# BlueLed.net
KiCad netlist of a schematic drawn in Altium Designer
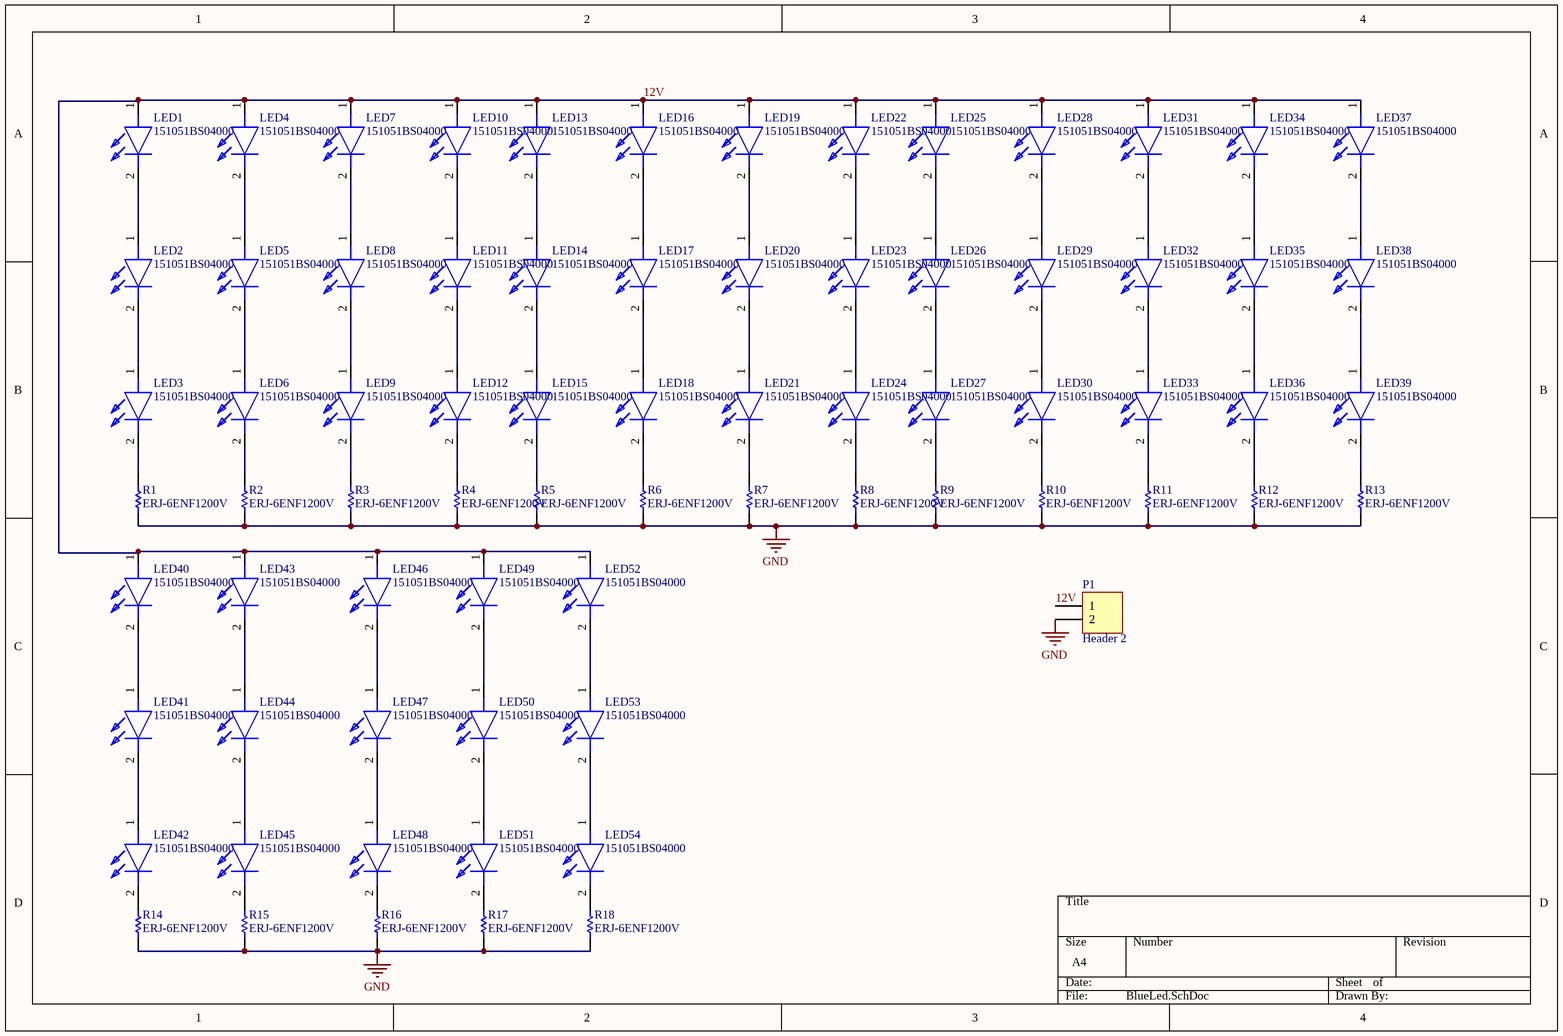
[diagram p0: BlueLed.SchDoc]

(export (version "E")
  (design (tool "Eeschema 10.0.6"))
  (components
    (comp (ref "LED1")
      (value "151051BS04000")
      (footprint "SamacSys:151051BS04000")
      (description "LED")
      (fields (field (name "MOUSER PART NUMBER") "710-151051BS04000"))
      (libsource (lib "*") (part "151051BS04000"))
    )
    (comp (ref "LED2")
      (value "151051BS04000")
      (footprint "SamacSys:151051BS04000")
      (description "LED")
      (fields (field (name "MOUSER PART NUMBER") "710-151051BS04000"))
      (libsource (lib "*") (part "151051BS04000"))
    )
    (comp (ref "LED3")
      (value "151051BS04000")
      (footprint "SamacSys:151051BS04000")
      (description "LED")
      (fields (field (name "MOUSER PART NUMBER") "710-151051BS04000"))
      (libsource (lib "*") (part "151051BS04000"))
    )
    (comp (ref "LED4")
      (value "151051BS04000")
      (footprint "SamacSys:151051BS04000")
      (description "LED")
      (fields (field (name "MOUSER PART NUMBER") "710-151051BS04000"))
      (libsource (lib "*") (part "151051BS04000"))
    )
    (comp (ref "LED5")
      (value "151051BS04000")
      (footprint "SamacSys:151051BS04000")
      (description "LED")
      (fields (field (name "MOUSER PART NUMBER") "710-151051BS04000"))
      (libsource (lib "*") (part "151051BS04000"))
    )
    (comp (ref "LED6")
      (value "151051BS04000")
      (footprint "SamacSys:151051BS04000")
      (description "LED")
      (fields (field (name "MOUSER PART NUMBER") "710-151051BS04000"))
      (libsource (lib "*") (part "151051BS04000"))
    )
    (comp (ref "LED7")
      (value "151051BS04000")
      (footprint "SamacSys:151051BS04000")
      (description "LED")
      (fields (field (name "MOUSER PART NUMBER") "710-151051BS04000"))
      (libsource (lib "*") (part "151051BS04000"))
    )
    (comp (ref "LED8")
      (value "151051BS04000")
      (footprint "SamacSys:151051BS04000")
      (description "LED")
      (fields (field (name "MOUSER PART NUMBER") "710-151051BS04000"))
      (libsource (lib "*") (part "151051BS04000"))
    )
    (comp (ref "LED9")
      (value "151051BS04000")
      (footprint "SamacSys:151051BS04000")
      (description "LED")
      (fields (field (name "MOUSER PART NUMBER") "710-151051BS04000"))
      (libsource (lib "*") (part "151051BS04000"))
    )
    (comp (ref "LED10")
      (value "151051BS04000")
      (footprint "SamacSys:151051BS04000")
      (description "LED")
      (fields (field (name "MOUSER PART NUMBER") "710-151051BS04000"))
      (libsource (lib "*") (part "151051BS04000"))
    )
    (comp (ref "LED11")
      (value "151051BS04000")
      (footprint "SamacSys:151051BS04000")
      (description "LED")
      (fields (field (name "MOUSER PART NUMBER") "710-151051BS04000"))
      (libsource (lib "*") (part "151051BS04000"))
    )
    (comp (ref "LED12")
      (value "151051BS04000")
      (footprint "SamacSys:151051BS04000")
      (description "LED")
      (fields (field (name "MOUSER PART NUMBER") "710-151051BS04000"))
      (libsource (lib "*") (part "151051BS04000"))
    )
    (comp (ref "LED13")
      (value "151051BS04000")
      (footprint "SamacSys:151051BS04000")
      (description "LED")
      (fields (field (name "MOUSER PART NUMBER") "710-151051BS04000"))
      (libsource (lib "*") (part "151051BS04000"))
    )
    (comp (ref "LED14")
      (value "151051BS04000")
      (footprint "SamacSys:151051BS04000")
      (description "LED")
      (fields (field (name "MOUSER PART NUMBER") "710-151051BS04000"))
      (libsource (lib "*") (part "151051BS04000"))
    )
    (comp (ref "LED15")
      (value "151051BS04000")
      (footprint "SamacSys:151051BS04000")
      (description "LED")
      (fields (field (name "MOUSER PART NUMBER") "710-151051BS04000"))
      (libsource (lib "*") (part "151051BS04000"))
    )
    (comp (ref "LED16")
      (value "151051BS04000")
      (footprint "SamacSys:151051BS04000")
      (description "LED")
      (fields (field (name "MOUSER PART NUMBER") "710-151051BS04000"))
      (libsource (lib "*") (part "151051BS04000"))
    )
    (comp (ref "LED17")
      (value "151051BS04000")
      (footprint "SamacSys:151051BS04000")
      (description "LED")
      (fields (field (name "MOUSER PART NUMBER") "710-151051BS04000"))
      (libsource (lib "*") (part "151051BS04000"))
    )
    (comp (ref "LED18")
      (value "151051BS04000")
      (footprint "SamacSys:151051BS04000")
      (description "LED")
      (fields (field (name "MOUSER PART NUMBER") "710-151051BS04000"))
      (libsource (lib "*") (part "151051BS04000"))
    )
    (comp (ref "LED19")
      (value "151051BS04000")
      (footprint "SamacSys:151051BS04000")
      (description "LED")
      (fields (field (name "MOUSER PART NUMBER") "710-151051BS04000"))
      (libsource (lib "*") (part "151051BS04000"))
    )
    (comp (ref "LED20")
      (value "151051BS04000")
      (footprint "SamacSys:151051BS04000")
      (description "LED")
      (fields (field (name "MOUSER PART NUMBER") "710-151051BS04000"))
      (libsource (lib "*") (part "151051BS04000"))
    )
    (comp (ref "LED21")
      (value "151051BS04000")
      (footprint "SamacSys:151051BS04000")
      (description "LED")
      (fields (field (name "MOUSER PART NUMBER") "710-151051BS04000"))
      (libsource (lib "*") (part "151051BS04000"))
    )
    (comp (ref "LED22")
      (value "151051BS04000")
      (footprint "SamacSys:151051BS04000")
      (description "LED")
      (fields (field (name "MOUSER PART NUMBER") "710-151051BS04000"))
      (libsource (lib "*") (part "151051BS04000"))
    )
    (comp (ref "LED23")
      (value "151051BS04000")
      (footprint "SamacSys:151051BS04000")
      (description "LED")
      (fields (field (name "MOUSER PART NUMBER") "710-151051BS04000"))
      (libsource (lib "*") (part "151051BS04000"))
    )
    (comp (ref "LED24")
      (value "151051BS04000")
      (footprint "SamacSys:151051BS04000")
      (description "LED")
      (fields (field (name "MOUSER PART NUMBER") "710-151051BS04000"))
      (libsource (lib "*") (part "151051BS04000"))
    )
    (comp (ref "LED25")
      (value "151051BS04000")
      (footprint "SamacSys:151051BS04000")
      (description "LED")
      (fields (field (name "MOUSER PART NUMBER") "710-151051BS04000"))
      (libsource (lib "*") (part "151051BS04000"))
    )
    (comp (ref "LED26")
      (value "151051BS04000")
      (footprint "SamacSys:151051BS04000")
      (description "LED")
      (fields (field (name "MOUSER PART NUMBER") "710-151051BS04000"))
      (libsource (lib "*") (part "151051BS04000"))
    )
    (comp (ref "LED27")
      (value "151051BS04000")
      (footprint "SamacSys:151051BS04000")
      (description "LED")
      (fields (field (name "MOUSER PART NUMBER") "710-151051BS04000"))
      (libsource (lib "*") (part "151051BS04000"))
    )
    (comp (ref "LED28")
      (value "151051BS04000")
      (footprint "SamacSys:151051BS04000")
      (description "LED")
      (fields (field (name "MOUSER PART NUMBER") "710-151051BS04000"))
      (libsource (lib "*") (part "151051BS04000"))
    )
    (comp (ref "LED29")
      (value "151051BS04000")
      (footprint "SamacSys:151051BS04000")
      (description "LED")
      (fields (field (name "MOUSER PART NUMBER") "710-151051BS04000"))
      (libsource (lib "*") (part "151051BS04000"))
    )
    (comp (ref "LED30")
      (value "151051BS04000")
      (footprint "SamacSys:151051BS04000")
      (description "LED")
      (fields (field (name "MOUSER PART NUMBER") "710-151051BS04000"))
      (libsource (lib "*") (part "151051BS04000"))
    )
    (comp (ref "LED31")
      (value "151051BS04000")
      (footprint "SamacSys:151051BS04000")
      (description "LED")
      (fields (field (name "MOUSER PART NUMBER") "710-151051BS04000"))
      (libsource (lib "*") (part "151051BS04000"))
    )
    (comp (ref "LED32")
      (value "151051BS04000")
      (footprint "SamacSys:151051BS04000")
      (description "LED")
      (fields (field (name "MOUSER PART NUMBER") "710-151051BS04000"))
      (libsource (lib "*") (part "151051BS04000"))
    )
    (comp (ref "LED33")
      (value "151051BS04000")
      (footprint "SamacSys:151051BS04000")
      (description "LED")
      (fields (field (name "MOUSER PART NUMBER") "710-151051BS04000"))
      (libsource (lib "*") (part "151051BS04000"))
    )
    (comp (ref "LED34")
      (value "151051BS04000")
      (footprint "SamacSys:151051BS04000")
      (description "LED")
      (fields (field (name "MOUSER PART NUMBER") "710-151051BS04000"))
      (libsource (lib "*") (part "151051BS04000"))
    )
    (comp (ref "LED35")
      (value "151051BS04000")
      (footprint "SamacSys:151051BS04000")
      (description "LED")
      (fields (field (name "MOUSER PART NUMBER") "710-151051BS04000"))
      (libsource (lib "*") (part "151051BS04000"))
    )
    (comp (ref "LED36")
      (value "151051BS04000")
      (footprint "SamacSys:151051BS04000")
      (description "LED")
      (fields (field (name "MOUSER PART NUMBER") "710-151051BS04000"))
      (libsource (lib "*") (part "151051BS04000"))
    )
    (comp (ref "LED37")
      (value "151051BS04000")
      (footprint "SamacSys:151051BS04000")
      (description "LED")
      (fields (field (name "MOUSER PART NUMBER") "710-151051BS04000"))
      (libsource (lib "*") (part "151051BS04000"))
    )
    (comp (ref "LED38")
      (value "151051BS04000")
      (footprint "SamacSys:151051BS04000")
      (description "LED")
      (fields (field (name "MOUSER PART NUMBER") "710-151051BS04000"))
      (libsource (lib "*") (part "151051BS04000"))
    )
    (comp (ref "LED39")
      (value "151051BS04000")
      (footprint "SamacSys:151051BS04000")
      (description "LED")
      (fields (field (name "MOUSER PART NUMBER") "710-151051BS04000"))
      (libsource (lib "*") (part "151051BS04000"))
    )
    (comp (ref "LED40")
      (value "151051BS04000")
      (footprint "SamacSys:151051BS04000")
      (description "LED")
      (fields (field (name "MOUSER PART NUMBER") "710-151051BS04000"))
      (libsource (lib "*") (part "151051BS04000"))
    )
    (comp (ref "LED41")
      (value "151051BS04000")
      (footprint "SamacSys:151051BS04000")
      (description "LED")
      (fields (field (name "MOUSER PART NUMBER") "710-151051BS04000"))
      (libsource (lib "*") (part "151051BS04000"))
    )
    (comp (ref "LED42")
      (value "151051BS04000")
      (footprint "SamacSys:151051BS04000")
      (description "LED")
      (fields (field (name "MOUSER PART NUMBER") "710-151051BS04000"))
      (libsource (lib "*") (part "151051BS04000"))
    )
    (comp (ref "LED43")
      (value "151051BS04000")
      (footprint "SamacSys:151051BS04000")
      (description "LED")
      (fields (field (name "MOUSER PART NUMBER") "710-151051BS04000"))
      (libsource (lib "*") (part "151051BS04000"))
    )
    (comp (ref "LED44")
      (value "151051BS04000")
      (footprint "SamacSys:151051BS04000")
      (description "LED")
      (fields (field (name "MOUSER PART NUMBER") "710-151051BS04000"))
      (libsource (lib "*") (part "151051BS04000"))
    )
    (comp (ref "LED45")
      (value "151051BS04000")
      (footprint "SamacSys:151051BS04000")
      (description "LED")
      (fields (field (name "MOUSER PART NUMBER") "710-151051BS04000"))
      (libsource (lib "*") (part "151051BS04000"))
    )
    (comp (ref "LED46")
      (value "151051BS04000")
      (footprint "SamacSys:151051BS04000")
      (description "LED")
      (fields (field (name "MOUSER PART NUMBER") "710-151051BS04000"))
      (libsource (lib "*") (part "151051BS04000"))
    )
    (comp (ref "LED47")
      (value "151051BS04000")
      (footprint "SamacSys:151051BS04000")
      (description "LED")
      (fields (field (name "MOUSER PART NUMBER") "710-151051BS04000"))
      (libsource (lib "*") (part "151051BS04000"))
    )
    (comp (ref "LED48")
      (value "151051BS04000")
      (footprint "SamacSys:151051BS04000")
      (description "LED")
      (fields (field (name "MOUSER PART NUMBER") "710-151051BS04000"))
      (libsource (lib "*") (part "151051BS04000"))
    )
    (comp (ref "LED49")
      (value "151051BS04000")
      (footprint "SamacSys:151051BS04000")
      (description "LED")
      (fields (field (name "MOUSER PART NUMBER") "710-151051BS04000"))
      (libsource (lib "*") (part "151051BS04000"))
    )
    (comp (ref "LED50")
      (value "151051BS04000")
      (footprint "SamacSys:151051BS04000")
      (description "LED")
      (fields (field (name "MOUSER PART NUMBER") "710-151051BS04000"))
      (libsource (lib "*") (part "151051BS04000"))
    )
    (comp (ref "LED51")
      (value "151051BS04000")
      (footprint "SamacSys:151051BS04000")
      (description "LED")
      (fields (field (name "MOUSER PART NUMBER") "710-151051BS04000"))
      (libsource (lib "*") (part "151051BS04000"))
    )
    (comp (ref "LED52")
      (value "151051BS04000")
      (footprint "SamacSys:151051BS04000")
      (description "LED")
      (fields (field (name "MOUSER PART NUMBER") "710-151051BS04000"))
      (libsource (lib "*") (part "151051BS04000"))
    )
    (comp (ref "LED53")
      (value "151051BS04000")
      (footprint "SamacSys:151051BS04000")
      (description "LED")
      (fields (field (name "MOUSER PART NUMBER") "710-151051BS04000"))
      (libsource (lib "*") (part "151051BS04000"))
    )
    (comp (ref "LED54")
      (value "151051BS04000")
      (footprint "SamacSys:151051BS04000")
      (description "LED")
      (fields (field (name "MOUSER PART NUMBER") "710-151051BS04000"))
      (libsource (lib "*") (part "151051BS04000"))
    )
    (comp (ref "P1")
      (value "Header 2")
      (footprint "HDR1X2")
      (description "Header, 2-Pin")
      (fields (field (name "PUBLISHER") "Altium Limited"))
      (libsource (lib "Miscellaneous Connectors") (part "Header 2"))
    )
    (comp (ref "R1")
      (value "ERJ-6ENF1200V")
      (footprint "RESC2013X70X40NL20T20")
      (description "Chip Resistor, 120 Ohm, +/- 1%, 0.125 W, -55 to 155 degC, 0805 (2012 Metric), RoHS, Tape and Reel")
      (fields (field (name "MANUFACTURER") "Panasonic"))
      (libsource (lib "Altium Content Vault") (part "RES-2"))
    )
    (comp (ref "R2")
      (value "ERJ-6ENF1200V")
      (footprint "RESC2013X70X40NL20T20")
      (description "Chip Resistor, 120 Ohm, +/- 1%, 0.125 W, -55 to 155 degC, 0805 (2012 Metric), RoHS, Tape and Reel")
      (fields (field (name "MANUFACTURER") "Panasonic"))
      (libsource (lib "Altium Content Vault") (part "RES-2"))
    )
    (comp (ref "R3")
      (value "ERJ-6ENF1200V")
      (footprint "RESC2013X70X40NL20T20")
      (description "Chip Resistor, 120 Ohm, +/- 1%, 0.125 W, -55 to 155 degC, 0805 (2012 Metric), RoHS, Tape and Reel")
      (fields (field (name "MANUFACTURER") "Panasonic"))
      (libsource (lib "Altium Content Vault") (part "RES-2"))
    )
    (comp (ref "R4")
      (value "ERJ-6ENF1200V")
      (footprint "RESC2013X70X40NL20T20")
      (description "Chip Resistor, 120 Ohm, +/- 1%, 0.125 W, -55 to 155 degC, 0805 (2012 Metric), RoHS, Tape and Reel")
      (fields (field (name "MANUFACTURER") "Panasonic"))
      (libsource (lib "Altium Content Vault") (part "RES-2"))
    )
    (comp (ref "R5")
      (value "ERJ-6ENF1200V")
      (footprint "RESC2013X70X40NL20T20")
      (description "Chip Resistor, 120 Ohm, +/- 1%, 0.125 W, -55 to 155 degC, 0805 (2012 Metric), RoHS, Tape and Reel")
      (fields (field (name "MANUFACTURER") "Panasonic"))
      (libsource (lib "Altium Content Vault") (part "RES-2"))
    )
    (comp (ref "R6")
      (value "ERJ-6ENF1200V")
      (footprint "RESC2013X70X40NL20T20")
      (description "Chip Resistor, 120 Ohm, +/- 1%, 0.125 W, -55 to 155 degC, 0805 (2012 Metric), RoHS, Tape and Reel")
      (fields (field (name "MANUFACTURER") "Panasonic"))
      (libsource (lib "Altium Content Vault") (part "RES-2"))
    )
    (comp (ref "R7")
      (value "ERJ-6ENF1200V")
      (footprint "RESC2013X70X40NL20T20")
      (description "Chip Resistor, 120 Ohm, +/- 1%, 0.125 W, -55 to 155 degC, 0805 (2012 Metric), RoHS, Tape and Reel")
      (fields (field (name "MANUFACTURER") "Panasonic"))
      (libsource (lib "Altium Content Vault") (part "RES-2"))
    )
    (comp (ref "R8")
      (value "ERJ-6ENF1200V")
      (footprint "RESC2013X70X40NL20T20")
      (description "Chip Resistor, 120 Ohm, +/- 1%, 0.125 W, -55 to 155 degC, 0805 (2012 Metric), RoHS, Tape and Reel")
      (fields (field (name "MANUFACTURER") "Panasonic"))
      (libsource (lib "Altium Content Vault") (part "RES-2"))
    )
    (comp (ref "R9")
      (value "ERJ-6ENF1200V")
      (footprint "RESC2013X70X40NL20T20")
      (description "Chip Resistor, 120 Ohm, +/- 1%, 0.125 W, -55 to 155 degC, 0805 (2012 Metric), RoHS, Tape and Reel")
      (fields (field (name "MANUFACTURER") "Panasonic"))
      (libsource (lib "Altium Content Vault") (part "RES-2"))
    )
    (comp (ref "R10")
      (value "ERJ-6ENF1200V")
      (footprint "RESC2013X70X40NL20T20")
      (description "Chip Resistor, 120 Ohm, +/- 1%, 0.125 W, -55 to 155 degC, 0805 (2012 Metric), RoHS, Tape and Reel")
      (fields (field (name "MANUFACTURER") "Panasonic"))
      (libsource (lib "Altium Content Vault") (part "RES-2"))
    )
    (comp (ref "R11")
      (value "ERJ-6ENF1200V")
      (footprint "RESC2013X70X40NL20T20")
      (description "Chip Resistor, 120 Ohm, +/- 1%, 0.125 W, -55 to 155 degC, 0805 (2012 Metric), RoHS, Tape and Reel")
      (fields (field (name "MANUFACTURER") "Panasonic"))
      (libsource (lib "Altium Content Vault") (part "RES-2"))
    )
    (comp (ref "R12")
      (value "ERJ-6ENF1200V")
      (footprint "RESC2013X70X40NL20T20")
      (description "Chip Resistor, 120 Ohm, +/- 1%, 0.125 W, -55 to 155 degC, 0805 (2012 Metric), RoHS, Tape and Reel")
      (fields (field (name "MANUFACTURER") "Panasonic"))
      (libsource (lib "Altium Content Vault") (part "RES-2"))
    )
    (comp (ref "R13")
      (value "ERJ-6ENF1200V")
      (footprint "RESC2013X70X40NL20T20")
      (description "Chip Resistor, 120 Ohm, +/- 1%, 0.125 W, -55 to 155 degC, 0805 (2012 Metric), RoHS, Tape and Reel")
      (fields (field (name "MANUFACTURER") "Panasonic"))
      (libsource (lib "Altium Content Vault") (part "RES-2"))
    )
    (comp (ref "R14")
      (value "ERJ-6ENF1200V")
      (footprint "RESC2013X70X40NL20T20")
      (description "Chip Resistor, 120 Ohm, +/- 1%, 0.125 W, -55 to 155 degC, 0805 (2012 Metric), RoHS, Tape and Reel")
      (fields (field (name "MANUFACTURER") "Panasonic"))
      (libsource (lib "Altium Content Vault") (part "RES-2"))
    )
    (comp (ref "R15")
      (value "ERJ-6ENF1200V")
      (footprint "RESC2013X70X40NL20T20")
      (description "Chip Resistor, 120 Ohm, +/- 1%, 0.125 W, -55 to 155 degC, 0805 (2012 Metric), RoHS, Tape and Reel")
      (fields (field (name "MANUFACTURER") "Panasonic"))
      (libsource (lib "Altium Content Vault") (part "RES-2"))
    )
    (comp (ref "R16")
      (value "ERJ-6ENF1200V")
      (footprint "RESC2013X70X40NL20T20")
      (description "Chip Resistor, 120 Ohm, +/- 1%, 0.125 W, -55 to 155 degC, 0805 (2012 Metric), RoHS, Tape and Reel")
      (fields (field (name "MANUFACTURER") "Panasonic"))
      (libsource (lib "Altium Content Vault") (part "RES-2"))
    )
    (comp (ref "R17")
      (value "ERJ-6ENF1200V")
      (footprint "RESC2013X70X40NL20T20")
      (description "Chip Resistor, 120 Ohm, +/- 1%, 0.125 W, -55 to 155 degC, 0805 (2012 Metric), RoHS, Tape and Reel")
      (fields (field (name "MANUFACTURER") "Panasonic"))
      (libsource (lib "Altium Content Vault") (part "RES-2"))
    )
    (comp (ref "R18")
      (value "ERJ-6ENF1200V")
      (footprint "RESC2013X70X40NL20T20")
      (description "Chip Resistor, 120 Ohm, +/- 1%, 0.125 W, -55 to 155 degC, 0805 (2012 Metric), RoHS, Tape and Reel")
      (fields (field (name "MANUFACTURER") "Panasonic"))
      (libsource (lib "Altium Content Vault") (part "RES-2"))
    )
  )
  (nets
    (net (code "1") (name "/12V") (class "Default")
      (node (ref "LED1") (pin "1") (pinfunction "A_1") (pintype "passive"))
      (node (ref "LED10") (pin "1") (pinfunction "A_1") (pintype "passive"))
      (node (ref "LED13") (pin "1") (pinfunction "A_1") (pintype "passive"))
      (node (ref "LED16") (pin "1") (pinfunction "A_1") (pintype "passive"))
      (node (ref "LED19") (pin "1") (pinfunction "A_1") (pintype "passive"))
      (node (ref "LED22") (pin "1") (pinfunction "A_1") (pintype "passive"))
      (node (ref "LED25") (pin "1") (pinfunction "A_1") (pintype "passive"))
      (node (ref "LED28") (pin "1") (pinfunction "A_1") (pintype "passive"))
      (node (ref "LED31") (pin "1") (pinfunction "A_1") (pintype "passive"))
      (node (ref "LED34") (pin "1") (pinfunction "A_1") (pintype "passive"))
      (node (ref "LED37") (pin "1") (pinfunction "A_1") (pintype "passive"))
      (node (ref "LED4") (pin "1") (pinfunction "A_1") (pintype "passive"))
      (node (ref "LED40") (pin "1") (pinfunction "A_1") (pintype "passive"))
      (node (ref "LED43") (pin "1") (pinfunction "A_1") (pintype "passive"))
      (node (ref "LED46") (pin "1") (pinfunction "A_1") (pintype "passive"))
      (node (ref "LED49") (pin "1") (pinfunction "A_1") (pintype "passive"))
      (node (ref "LED52") (pin "1") (pinfunction "A_1") (pintype "passive"))
      (node (ref "LED7") (pin "1") (pinfunction "A_1") (pintype "passive"))
      (node (ref "P1") (pin "1") (pinfunction "1_1") (pintype "passive"))
    )
    (net (code "2") (name "GND") (class "Default")
      (node (ref "P1") (pin "2") (pinfunction "2_2") (pintype "passive"))
      (node (ref "R1") (pin "1") (pinfunction "1_1") (pintype "passive"))
      (node (ref "R10") (pin "1") (pinfunction "1_1") (pintype "passive"))
      (node (ref "R11") (pin "1") (pinfunction "1_1") (pintype "passive"))
      (node (ref "R12") (pin "1") (pinfunction "1_1") (pintype "passive"))
      (node (ref "R13") (pin "1") (pinfunction "1_1") (pintype "passive"))
      (node (ref "R14") (pin "1") (pinfunction "1_1") (pintype "passive"))
      (node (ref "R15") (pin "1") (pinfunction "1_1") (pintype "passive"))
      (node (ref "R16") (pin "1") (pinfunction "1_1") (pintype "passive"))
      (node (ref "R17") (pin "1") (pinfunction "1_1") (pintype "passive"))
      (node (ref "R18") (pin "1") (pinfunction "1_1") (pintype "passive"))
      (node (ref "R2") (pin "1") (pinfunction "1_1") (pintype "passive"))
      (node (ref "R3") (pin "1") (pinfunction "1_1") (pintype "passive"))
      (node (ref "R4") (pin "1") (pinfunction "1_1") (pintype "passive"))
      (node (ref "R5") (pin "1") (pinfunction "1_1") (pintype "passive"))
      (node (ref "R6") (pin "1") (pinfunction "1_1") (pintype "passive"))
      (node (ref "R7") (pin "1") (pinfunction "1_1") (pintype "passive"))
      (node (ref "R8") (pin "1") (pinfunction "1_1") (pintype "passive"))
      (node (ref "R9") (pin "1") (pinfunction "1_1") (pintype "passive"))
    )
    (net (code "3") (name "Net-(LED1-K)") (class "Default")
      (node (ref "LED1") (pin "2") (pinfunction "K_2") (pintype "passive"))
      (node (ref "LED2") (pin "1") (pinfunction "A_1") (pintype "passive"))
    )
    (net (code "4") (name "Net-(LED2-K)") (class "Default")
      (node (ref "LED2") (pin "2") (pinfunction "K_2") (pintype "passive"))
      (node (ref "LED3") (pin "1") (pinfunction "A_1") (pintype "passive"))
    )
    (net (code "5") (name "Net-(LED3-K)") (class "Default")
      (node (ref "LED3") (pin "2") (pinfunction "K_2") (pintype "passive"))
      (node (ref "R1") (pin "2") (pinfunction "2_2") (pintype "passive"))
    )
    (net (code "6") (name "Net-(LED4-K)") (class "Default")
      (node (ref "LED4") (pin "2") (pinfunction "K_2") (pintype "passive"))
      (node (ref "LED5") (pin "1") (pinfunction "A_1") (pintype "passive"))
    )
    (net (code "7") (name "Net-(LED5-K)") (class "Default")
      (node (ref "LED5") (pin "2") (pinfunction "K_2") (pintype "passive"))
      (node (ref "LED6") (pin "1") (pinfunction "A_1") (pintype "passive"))
    )
    (net (code "8") (name "Net-(LED6-K)") (class "Default")
      (node (ref "LED6") (pin "2") (pinfunction "K_2") (pintype "passive"))
      (node (ref "R2") (pin "2") (pinfunction "2_2") (pintype "passive"))
    )
    (net (code "9") (name "Net-(LED7-K)") (class "Default")
      (node (ref "LED7") (pin "2") (pinfunction "K_2") (pintype "passive"))
      (node (ref "LED8") (pin "1") (pinfunction "A_1") (pintype "passive"))
    )
    (net (code "10") (name "Net-(LED8-K)") (class "Default")
      (node (ref "LED8") (pin "2") (pinfunction "K_2") (pintype "passive"))
      (node (ref "LED9") (pin "1") (pinfunction "A_1") (pintype "passive"))
    )
    (net (code "11") (name "Net-(LED9-K)") (class "Default")
      (node (ref "LED9") (pin "2") (pinfunction "K_2") (pintype "passive"))
      (node (ref "R3") (pin "2") (pinfunction "2_2") (pintype "passive"))
    )
    (net (code "12") (name "Net-(LED10-K)") (class "Default")
      (node (ref "LED10") (pin "2") (pinfunction "K_2") (pintype "passive"))
      (node (ref "LED11") (pin "1") (pinfunction "A_1") (pintype "passive"))
    )
    (net (code "13") (name "Net-(LED11-K)") (class "Default")
      (node (ref "LED11") (pin "2") (pinfunction "K_2") (pintype "passive"))
      (node (ref "LED12") (pin "1") (pinfunction "A_1") (pintype "passive"))
    )
    (net (code "14") (name "Net-(LED12-K)") (class "Default")
      (node (ref "LED12") (pin "2") (pinfunction "K_2") (pintype "passive"))
      (node (ref "R4") (pin "2") (pinfunction "2_2") (pintype "passive"))
    )
    (net (code "15") (name "Net-(LED13-K)") (class "Default")
      (node (ref "LED13") (pin "2") (pinfunction "K_2") (pintype "passive"))
      (node (ref "LED14") (pin "1") (pinfunction "A_1") (pintype "passive"))
    )
    (net (code "16") (name "Net-(LED14-K)") (class "Default")
      (node (ref "LED14") (pin "2") (pinfunction "K_2") (pintype "passive"))
      (node (ref "LED15") (pin "1") (pinfunction "A_1") (pintype "passive"))
    )
    (net (code "17") (name "Net-(LED15-K)") (class "Default")
      (node (ref "LED15") (pin "2") (pinfunction "K_2") (pintype "passive"))
      (node (ref "R5") (pin "2") (pinfunction "2_2") (pintype "passive"))
    )
    (net (code "18") (name "Net-(LED16-K)") (class "Default")
      (node (ref "LED16") (pin "2") (pinfunction "K_2") (pintype "passive"))
      (node (ref "LED17") (pin "1") (pinfunction "A_1") (pintype "passive"))
    )
    (net (code "19") (name "Net-(LED17-K)") (class "Default")
      (node (ref "LED17") (pin "2") (pinfunction "K_2") (pintype "passive"))
      (node (ref "LED18") (pin "1") (pinfunction "A_1") (pintype "passive"))
    )
    (net (code "20") (name "Net-(LED18-K)") (class "Default")
      (node (ref "LED18") (pin "2") (pinfunction "K_2") (pintype "passive"))
      (node (ref "R6") (pin "2") (pinfunction "2_2") (pintype "passive"))
    )
    (net (code "21") (name "Net-(LED19-K)") (class "Default")
      (node (ref "LED19") (pin "2") (pinfunction "K_2") (pintype "passive"))
      (node (ref "LED20") (pin "1") (pinfunction "A_1") (pintype "passive"))
    )
    (net (code "22") (name "Net-(LED20-K)") (class "Default")
      (node (ref "LED20") (pin "2") (pinfunction "K_2") (pintype "passive"))
      (node (ref "LED21") (pin "1") (pinfunction "A_1") (pintype "passive"))
    )
    (net (code "23") (name "Net-(LED21-K)") (class "Default")
      (node (ref "LED21") (pin "2") (pinfunction "K_2") (pintype "passive"))
      (node (ref "R7") (pin "2") (pinfunction "2_2") (pintype "passive"))
    )
    (net (code "24") (name "Net-(LED22-K)") (class "Default")
      (node (ref "LED22") (pin "2") (pinfunction "K_2") (pintype "passive"))
      (node (ref "LED23") (pin "1") (pinfunction "A_1") (pintype "passive"))
    )
    (net (code "25") (name "Net-(LED23-K)") (class "Default")
      (node (ref "LED23") (pin "2") (pinfunction "K_2") (pintype "passive"))
      (node (ref "LED24") (pin "1") (pinfunction "A_1") (pintype "passive"))
    )
    (net (code "26") (name "Net-(LED24-K)") (class "Default")
      (node (ref "LED24") (pin "2") (pinfunction "K_2") (pintype "passive"))
      (node (ref "R8") (pin "2") (pinfunction "2_2") (pintype "passive"))
    )
    (net (code "27") (name "Net-(LED25-K)") (class "Default")
      (node (ref "LED25") (pin "2") (pinfunction "K_2") (pintype "passive"))
      (node (ref "LED26") (pin "1") (pinfunction "A_1") (pintype "passive"))
    )
    (net (code "28") (name "Net-(LED26-K)") (class "Default")
      (node (ref "LED26") (pin "2") (pinfunction "K_2") (pintype "passive"))
      (node (ref "LED27") (pin "1") (pinfunction "A_1") (pintype "passive"))
    )
    (net (code "29") (name "Net-(LED27-K)") (class "Default")
      (node (ref "LED27") (pin "2") (pinfunction "K_2") (pintype "passive"))
      (node (ref "R9") (pin "2") (pinfunction "2_2") (pintype "passive"))
    )
    (net (code "30") (name "Net-(LED28-K)") (class "Default")
      (node (ref "LED28") (pin "2") (pinfunction "K_2") (pintype "passive"))
      (node (ref "LED29") (pin "1") (pinfunction "A_1") (pintype "passive"))
    )
    (net (code "31") (name "Net-(LED29-K)") (class "Default")
      (node (ref "LED29") (pin "2") (pinfunction "K_2") (pintype "passive"))
      (node (ref "LED30") (pin "1") (pinfunction "A_1") (pintype "passive"))
    )
    (net (code "32") (name "Net-(LED30-K)") (class "Default")
      (node (ref "LED30") (pin "2") (pinfunction "K_2") (pintype "passive"))
      (node (ref "R10") (pin "2") (pinfunction "2_2") (pintype "passive"))
    )
    (net (code "33") (name "Net-(LED31-K)") (class "Default")
      (node (ref "LED31") (pin "2") (pinfunction "K_2") (pintype "passive"))
      (node (ref "LED32") (pin "1") (pinfunction "A_1") (pintype "passive"))
    )
    (net (code "34") (name "Net-(LED32-K)") (class "Default")
      (node (ref "LED32") (pin "2") (pinfunction "K_2") (pintype "passive"))
      (node (ref "LED33") (pin "1") (pinfunction "A_1") (pintype "passive"))
    )
    (net (code "35") (name "Net-(LED33-K)") (class "Default")
      (node (ref "LED33") (pin "2") (pinfunction "K_2") (pintype "passive"))
      (node (ref "R11") (pin "2") (pinfunction "2_2") (pintype "passive"))
    )
    (net (code "36") (name "Net-(LED34-K)") (class "Default")
      (node (ref "LED34") (pin "2") (pinfunction "K_2") (pintype "passive"))
      (node (ref "LED35") (pin "1") (pinfunction "A_1") (pintype "passive"))
    )
    (net (code "37") (name "Net-(LED35-K)") (class "Default")
      (node (ref "LED35") (pin "2") (pinfunction "K_2") (pintype "passive"))
      (node (ref "LED36") (pin "1") (pinfunction "A_1") (pintype "passive"))
    )
    (net (code "38") (name "Net-(LED36-K)") (class "Default")
      (node (ref "LED36") (pin "2") (pinfunction "K_2") (pintype "passive"))
      (node (ref "R12") (pin "2") (pinfunction "2_2") (pintype "passive"))
    )
    (net (code "39") (name "Net-(LED37-K)") (class "Default")
      (node (ref "LED37") (pin "2") (pinfunction "K_2") (pintype "passive"))
      (node (ref "LED38") (pin "1") (pinfunction "A_1") (pintype "passive"))
    )
    (net (code "40") (name "Net-(LED38-K)") (class "Default")
      (node (ref "LED38") (pin "2") (pinfunction "K_2") (pintype "passive"))
      (node (ref "LED39") (pin "1") (pinfunction "A_1") (pintype "passive"))
    )
    (net (code "41") (name "Net-(LED39-K)") (class "Default")
      (node (ref "LED39") (pin "2") (pinfunction "K_2") (pintype "passive"))
      (node (ref "R13") (pin "2") (pinfunction "2_2") (pintype "passive"))
    )
    (net (code "42") (name "Net-(LED40-K)") (class "Default")
      (node (ref "LED40") (pin "2") (pinfunction "K_2") (pintype "passive"))
      (node (ref "LED41") (pin "1") (pinfunction "A_1") (pintype "passive"))
    )
    (net (code "43") (name "Net-(LED41-K)") (class "Default")
      (node (ref "LED41") (pin "2") (pinfunction "K_2") (pintype "passive"))
      (node (ref "LED42") (pin "1") (pinfunction "A_1") (pintype "passive"))
    )
    (net (code "44") (name "Net-(LED42-K)") (class "Default")
      (node (ref "LED42") (pin "2") (pinfunction "K_2") (pintype "passive"))
      (node (ref "R14") (pin "2") (pinfunction "2_2") (pintype "passive"))
    )
    (net (code "45") (name "Net-(LED43-K)") (class "Default")
      (node (ref "LED43") (pin "2") (pinfunction "K_2") (pintype "passive"))
      (node (ref "LED44") (pin "1") (pinfunction "A_1") (pintype "passive"))
    )
    (net (code "46") (name "Net-(LED44-K)") (class "Default")
      (node (ref "LED44") (pin "2") (pinfunction "K_2") (pintype "passive"))
      (node (ref "LED45") (pin "1") (pinfunction "A_1") (pintype "passive"))
    )
    (net (code "47") (name "Net-(LED45-K)") (class "Default")
      (node (ref "LED45") (pin "2") (pinfunction "K_2") (pintype "passive"))
      (node (ref "R15") (pin "2") (pinfunction "2_2") (pintype "passive"))
    )
    (net (code "48") (name "Net-(LED46-K)") (class "Default")
      (node (ref "LED46") (pin "2") (pinfunction "K_2") (pintype "passive"))
      (node (ref "LED47") (pin "1") (pinfunction "A_1") (pintype "passive"))
    )
    (net (code "49") (name "Net-(LED47-K)") (class "Default")
      (node (ref "LED47") (pin "2") (pinfunction "K_2") (pintype "passive"))
      (node (ref "LED48") (pin "1") (pinfunction "A_1") (pintype "passive"))
    )
    (net (code "50") (name "Net-(LED48-K)") (class "Default")
      (node (ref "LED48") (pin "2") (pinfunction "K_2") (pintype "passive"))
      (node (ref "R16") (pin "2") (pinfunction "2_2") (pintype "passive"))
    )
    (net (code "51") (name "Net-(LED49-K)") (class "Default")
      (node (ref "LED49") (pin "2") (pinfunction "K_2") (pintype "passive"))
      (node (ref "LED50") (pin "1") (pinfunction "A_1") (pintype "passive"))
    )
    (net (code "52") (name "Net-(LED50-K)") (class "Default")
      (node (ref "LED50") (pin "2") (pinfunction "K_2") (pintype "passive"))
      (node (ref "LED51") (pin "1") (pinfunction "A_1") (pintype "passive"))
    )
    (net (code "53") (name "Net-(LED51-K)") (class "Default")
      (node (ref "LED51") (pin "2") (pinfunction "K_2") (pintype "passive"))
      (node (ref "R17") (pin "2") (pinfunction "2_2") (pintype "passive"))
    )
    (net (code "54") (name "Net-(LED52-K)") (class "Default")
      (node (ref "LED52") (pin "2") (pinfunction "K_2") (pintype "passive"))
      (node (ref "LED53") (pin "1") (pinfunction "A_1") (pintype "passive"))
    )
    (net (code "55") (name "Net-(LED53-K)") (class "Default")
      (node (ref "LED53") (pin "2") (pinfunction "K_2") (pintype "passive"))
      (node (ref "LED54") (pin "1") (pinfunction "A_1") (pintype "passive"))
    )
    (net (code "56") (name "Net-(LED54-K)") (class "Default")
      (node (ref "LED54") (pin "2") (pinfunction "K_2") (pintype "passive"))
      (node (ref "R18") (pin "2") (pinfunction "2_2") (pintype "passive"))
    )
  )
)
